# design.net
KiCad netlist of a schematic drawn in Altium Designer
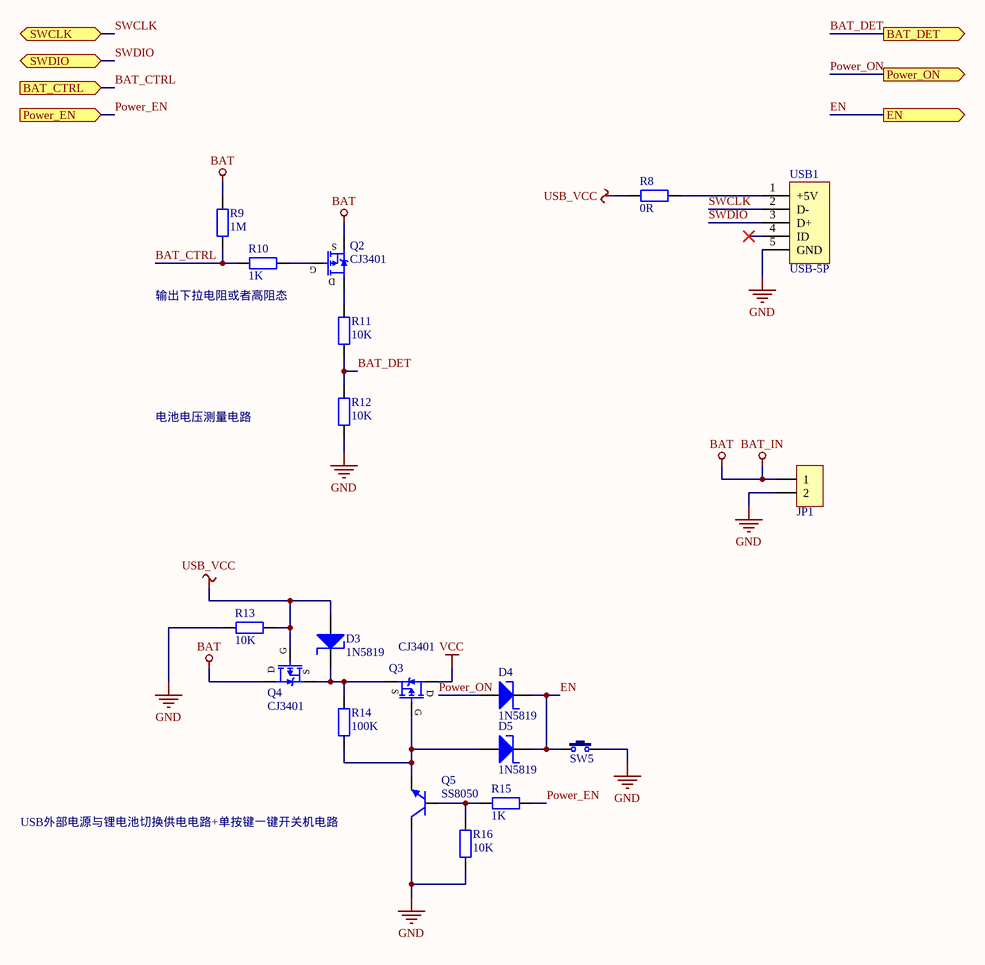
[diagram p0: 电池模块.SchDoc]

(export (version "E")
  (design (tool "Eeschema 10.0.6"))
  (components
    (comp (ref "D3")
      (value "1N5819")
      (footprint "SOD-323")
      (description "肖特基二极管")
      (fields (field (name "版权归属") "源创客"))
      (libsource (lib "8.1   - 二极管-整流桥") (part "1N5819"))
    )
    (comp (ref "D4")
      (value "1N5819")
      (footprint "SOD-323")
      (description "肖特基二极管")
      (fields (field (name "版权归属") "源创客"))
      (libsource (lib "8.1   - 二极管-整流桥") (part "1N5819"))
    )
    (comp (ref "D5")
      (value "1N5819")
      (footprint "SOD-323")
      (description "肖特基二极管")
      (fields (field (name "版权归属") "源创客"))
      (libsource (lib "8.1   - 二极管-整流桥") (part "1N5819"))
    )
    (comp (ref "JP1")
      (value "HDR-1X2")
      (footprint "HDR2.54-LI-2P")
      (description "2P接插件")
      (fields (field (name "版权归属") "源创客"))
      (libsource (lib "4.6   - 接插件-脚距2.54") (part "Header 2"))
    )
    (comp (ref "Q2")
      (value "CJ3401")
      (footprint "SOT23-3L")
      (description "P沟道 30V/4.2A")
      (libsource (lib "6.1   - 场效应管-可控硅") (part "CJ3401"))
    )
    (comp (ref "Q3")
      (value "CJ3401")
      (footprint "SOT23-3L")
      (description "P沟道 30V/4.2A")
      (libsource (lib "6.1   - 场效应管-可控硅") (part "CJ3401"))
    )
    (comp (ref "Q4")
      (value "CJ3401")
      (footprint "SOT23-3L")
      (description "P沟道 30V/4.2A")
      (libsource (lib "6.1   - 场效应管-可控硅") (part "CJ3401"))
    )
    (comp (ref "Q5")
      (value "SS8050")
      (footprint "SOT23-3N")
      (description "高频放大-NPN型 丝印J3Y")
      (fields (field (name "版权归属") "源创客"))
      (libsource (lib "6.2   - 三极管") (part "8050-SMD"))
    )
    (comp (ref "R8")
      (value "0R")
      (footprint "R 0603_L")
      (description "贴片电阻")
      (fields (field (name "版权归属") "黎明电子style"))
      (libsource (lib "3.4   - 电阻Resistor") (part "R"))
    )
    (comp (ref "R9")
      (value "1M")
      (footprint "R 0603_L")
      (description "贴片电阻")
      (fields (field (name "版权归属") "黎明电子style"))
      (libsource (lib "3.4   - 电阻Resistor") (part "R"))
    )
    (comp (ref "R10")
      (value "1K")
      (footprint "R 0603_L")
      (description "贴片电阻")
      (fields (field (name "版权归属") "黎明电子style"))
      (libsource (lib "3.4   - 电阻Resistor") (part "R"))
    )
    (comp (ref "R11")
      (value "10K")
      (footprint "R 0603_L")
      (description "贴片电阻")
      (fields (field (name "版权归属") "黎明电子style"))
      (libsource (lib "3.4   - 电阻Resistor") (part "R"))
    )
    (comp (ref "R12")
      (value "10K")
      (footprint "R 0603_L")
      (description "贴片电阻")
      (fields (field (name "版权归属") "黎明电子style"))
      (libsource (lib "3.4   - 电阻Resistor") (part "R"))
    )
    (comp (ref "R13")
      (value "10K")
      (footprint "R 0603_L")
      (description "贴片电阻")
      (fields (field (name "版权归属") "黎明电子style"))
      (libsource (lib "3.4   - 电阻Resistor") (part "R"))
    )
    (comp (ref "R14")
      (value "100K")
      (footprint "R 0603_L")
      (description "贴片电阻")
      (fields (field (name "版权归属") "黎明电子style"))
      (libsource (lib "3.4   - 电阻Resistor") (part "R"))
    )
    (comp (ref "R15")
      (value "1K")
      (footprint "R 0603_L")
      (description "贴片电阻")
      (fields (field (name "版权归属") "黎明电子style"))
      (libsource (lib "3.4   - 电阻Resistor") (part "R"))
    )
    (comp (ref "R16")
      (value "10K")
      (footprint "R 0603_L")
      (description "贴片电阻")
      (fields (field (name "版权归属") "黎明电子style"))
      (libsource (lib "3.4   - 电阻Resistor") (part "R"))
    )
    (comp (ref "SW5")
      (value "3x6x5")
      (footprint "TSW 4.6*1.82*3.5-S-W")
      (description "3x6轻触开关")
      (fields (field (name "版权归属") "源创客"))
      (libsource (lib "5.1   - 按键-开关") (part "TSW 3x6"))
    )
    (comp (ref "USB1")
      (value "USB-5P")
      (footprint "USB-MICRO_A")
      (description "微型USB母座")
      (fields (field (name "版权归属") "源创客"))
      (libsource (lib "4.1   - 接口类") (part "USB-5P"))
    )
  )
  (nets
    (net (code "1") (name "/BAT_CTRL") (class "Default")
      (node (ref "R10") (pin "1") (pinfunction "1_1") (pintype "passive"))
      (node (ref "R9") (pin "2") (pinfunction "2_2") (pintype "passive"))
    )
    (net (code "2") (name "/BAT_DET") (class "Default")
      (node (ref "R11") (pin "2") (pinfunction "2_2") (pintype "passive"))
      (node (ref "R12") (pin "1") (pinfunction "1_1") (pintype "passive"))
    )
    (net (code "3") (name "/EN") (class "Default")
      (node (ref "D4") (pin "2") (pinfunction "K_2") (pintype "passive"))
      (node (ref "D5") (pin "2") (pinfunction "K_2") (pintype "passive"))
      (node (ref "SW5") (pin "1") (pinfunction "1_1") (pintype "passive"))
    )
    (net (code "4") (name "/Power_EN") (class "Default")
      (node (ref "R15") (pin "2") (pinfunction "2_2") (pintype "passive"))
    )
    (net (code "5") (name "/Power_ON") (class "Default")
      (node (ref "D4") (pin "1") (pinfunction "A_1") (pintype "passive"))
    )
    (net (code "6") (name "/SWCLK") (class "Default")
      (node (ref "USB1") (pin "2") (pinfunction "D-_2") (pintype "passive"))
    )
    (net (code "7") (name "/SWDIO") (class "Default")
      (node (ref "USB1") (pin "3") (pinfunction "D+_3") (pintype "passive"))
    )
    (net (code "8") (name "BAT") (class "Default")
      (node (ref "JP1") (pin "1") (pinfunction "1_1") (pintype "passive"))
      (node (ref "Q2") (pin "3") (pinfunction "D_3") (pintype "passive"))
      (node (ref "Q4") (pin "2") (pinfunction "S_2") (pintype "passive"))
      (node (ref "R9") (pin "1") (pinfunction "1_1") (pintype "passive"))
    )
    (net (code "9") (name "GND") (class "Default")
      (node (ref "JP1") (pin "2") (pinfunction "2_2") (pintype "passive"))
      (node (ref "Q5") (pin "3") (pinfunction "C_3") (pintype "passive"))
      (node (ref "R12") (pin "2") (pinfunction "2_2") (pintype "passive"))
      (node (ref "R13") (pin "2") (pinfunction "2_2") (pintype "passive"))
      (node (ref "R16") (pin "2") (pinfunction "2_2") (pintype "passive"))
      (node (ref "SW5") (pin "2") (pinfunction "2_2") (pintype "passive"))
      (node (ref "USB1") (pin "5") (pinfunction "GND_5") (pintype "passive"))
    )
    (net (code "10") (name "Net-(D3-K)") (class "Default")
      (node (ref "D3") (pin "2") (pinfunction "K_2") (pintype "passive"))
      (node (ref "Q3") (pin "3") (pinfunction "D_3") (pintype "passive"))
      (node (ref "Q4") (pin "3") (pinfunction "D_3") (pintype "passive"))
      (node (ref "R14") (pin "1") (pinfunction "1_1") (pintype "passive"))
    )
    (net (code "11") (name "Net-(D5-A)") (class "Default")
      (node (ref "D5") (pin "1") (pinfunction "A_1") (pintype "passive"))
      (node (ref "Q3") (pin "1") (pinfunction "G_1") (pintype "passive"))
      (node (ref "Q5") (pin "2") (pinfunction "E_2") (pintype "passive"))
      (node (ref "R14") (pin "2") (pinfunction "2_2") (pintype "passive"))
    )
    (net (code "12") (name "Net-(Q2-G)") (class "Default")
      (node (ref "Q2") (pin "1") (pinfunction "G_1") (pintype "passive"))
      (node (ref "R10") (pin "2") (pinfunction "2_2") (pintype "passive"))
    )
    (net (code "13") (name "Net-(Q2-S)") (class "Default")
      (node (ref "Q2") (pin "2") (pinfunction "S_2") (pintype "passive"))
      (node (ref "R11") (pin "1") (pinfunction "1_1") (pintype "passive"))
    )
    (net (code "14") (name "Net-(Q5-B)") (class "Default")
      (node (ref "Q5") (pin "1") (pinfunction "B_1") (pintype "passive"))
      (node (ref "R15") (pin "1") (pinfunction "1_1") (pintype "passive"))
      (node (ref "R16") (pin "1") (pinfunction "1_1") (pintype "passive"))
    )
    (net (code "15") (name "Net-(USB1-+5V)") (class "Default")
      (node (ref "R8") (pin "1") (pinfunction "1_1") (pintype "passive"))
      (node (ref "USB1") (pin "1") (pinfunction "+5V_1") (pintype "passive"))
    )
    (net (code "16") (name "USB_VCC") (class "Default")
      (node (ref "D3") (pin "1") (pinfunction "A_1") (pintype "passive"))
      (node (ref "Q4") (pin "1") (pinfunction "G_1") (pintype "passive"))
      (node (ref "R13") (pin "1") (pinfunction "1_1") (pintype "passive"))
      (node (ref "R8") (pin "2") (pinfunction "2_2") (pintype "passive"))
    )
    (net (code "17") (name "VCC") (class "Default")
      (node (ref "Q3") (pin "2") (pinfunction "S_2") (pintype "passive"))
    )
    (net (code "18") (name "unconnected-(USB1-ID-Pad4)") (class "Default")
      (node (ref "USB1") (pin "4") (pinfunction "ID_4") (pintype "passive+no_connect"))
    )
  )
)
